# SQUID_Power.net
KiCad netlist of a schematic drawn in Altium Designer
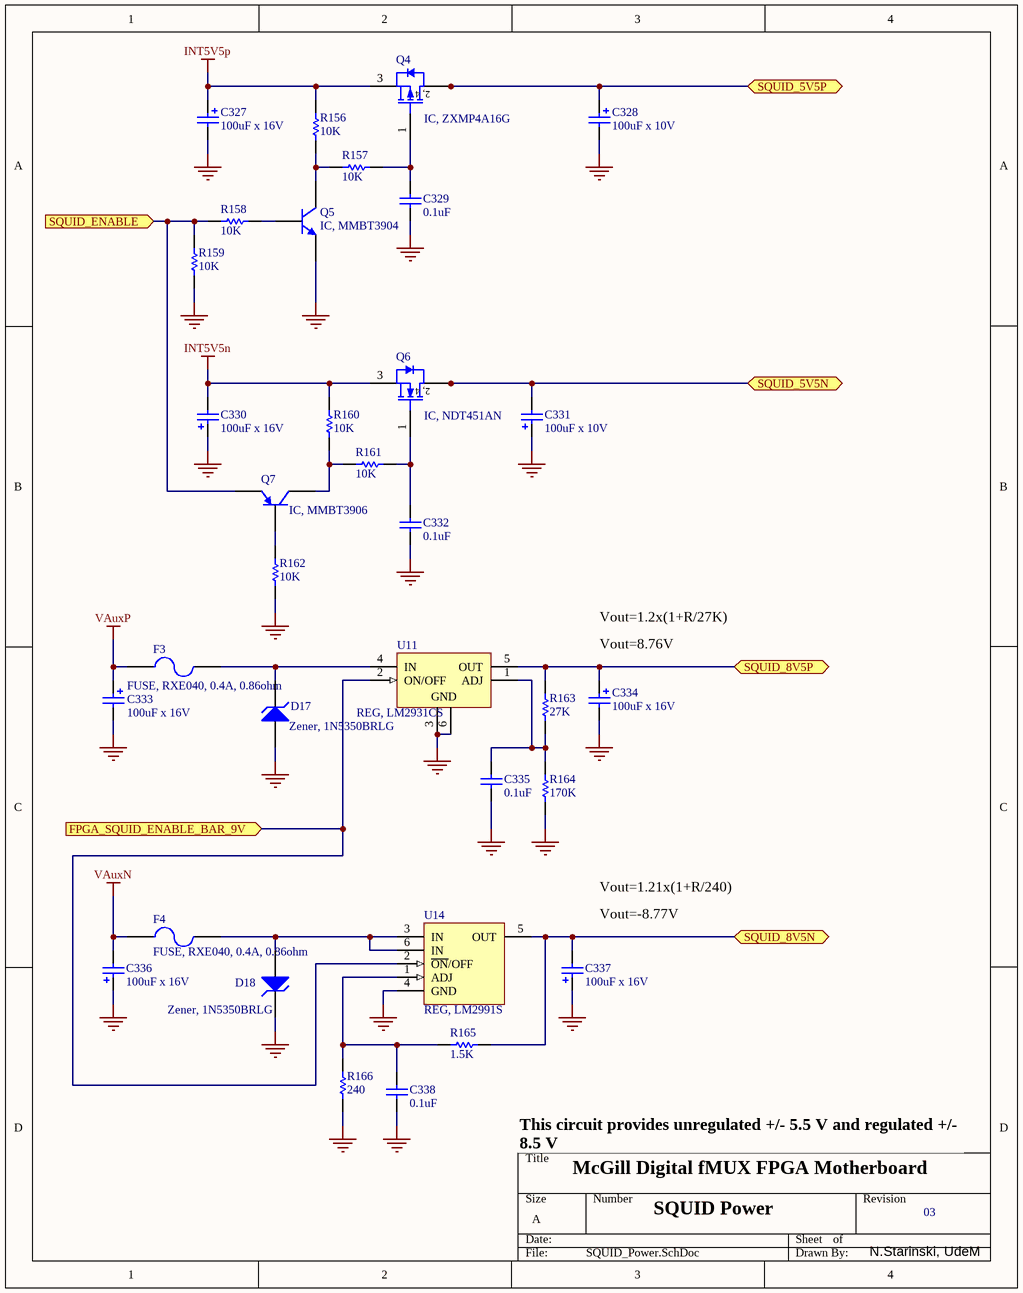
[diagram p0: SQUID_Power.SchDoc]

(export (version "E")
  (design (tool "Eeschema 10.0.6"))
  (components
    (comp (ref "C327")
      (value "100uF x 16V")
      (footprint "CC7343-31_Dsize")
      (description "CAP TANTD TPSD107M016R0060")
      (fields (field (name "PUBLISHER") "Altium Limited"))
      (libsource (lib "Miscellaneous Devices") (part "Cap Pol3"))
    )
    (comp (ref "C328")
      (value "100uF x 10V")
      (footprint "TC6032-2412")
      (description "CAP TANTC TPSC107K010R0075")
      (fields (field (name "PUBLISHER") "Altium Limited"))
      (libsource (lib "Miscellaneous Devices 02") (part "Cap Pol3"))
    )
    (comp (ref "C329")
      (value "0.1uF")
      (footprint "CC1608-0603")
      (description "Capacitor (Semiconductor SIM Model)")
      (fields (field (name "PUBLISHER") "Altium Limited"))
      (libsource (lib "Miscellaneous Devices") (part "Cap Semi"))
    )
    (comp (ref "C330")
      (value "100uF x 16V")
      (footprint "CC7343-31_Dsize")
      (description "CAP TANTD TPSD107M016R0060")
      (fields (field (name "PUBLISHER") "Altium Limited"))
      (libsource (lib "Miscellaneous Devices") (part "Cap Pol3"))
    )
    (comp (ref "C331")
      (value "100uF x 10V")
      (footprint "TC6032-2412")
      (description "CAP TANTC TPSC107K010R0075")
      (fields (field (name "PUBLISHER") "Altium Limited"))
      (libsource (lib "Miscellaneous Devices 02") (part "Cap Pol3"))
    )
    (comp (ref "C332")
      (value "0.1uF")
      (footprint "CC1608-0603")
      (description "Capacitor (Semiconductor SIM Model)")
      (fields (field (name "PUBLISHER") "Altium Limited"))
      (libsource (lib "Miscellaneous Devices") (part "Cap Semi"))
    )
    (comp (ref "C333")
      (value "100uF x 16V")
      (footprint "CC7343-31_Dsize")
      (description "CAP TANTD TPSD107M016R0060")
      (fields (field (name "PUBLISHER") "Altium Limited"))
      (libsource (lib "Miscellaneous Devices") (part "Cap Pol3"))
    )
    (comp (ref "C334")
      (value "100uF x 16V")
      (footprint "CC7343-31_Dsize")
      (description "CAP TANTD TPSD107M016R0060")
      (fields (field (name "PUBLISHER") "Altium Limited"))
      (libsource (lib "Miscellaneous Devices") (part "Cap Pol3"))
    )
    (comp (ref "C335")
      (value "0.1uF")
      (footprint "CC1608-0603")
      (description "Capacitor (Semiconductor SIM Model)")
      (fields (field (name "PUBLISHER") "Altium Limited"))
      (libsource (lib "Miscellaneous Devices") (part "Cap Semi"))
    )
    (comp (ref "C336")
      (value "100uF x 16V")
      (footprint "CC7343-31_Dsize")
      (description "CAP TANTD TPSD107M016R0060")
      (fields (field (name "PUBLISHER") "Altium Limited"))
      (libsource (lib "Miscellaneous Devices") (part "Cap Pol3"))
    )
    (comp (ref "C337")
      (value "100uF x 16V")
      (footprint "CC7343-31_Dsize")
      (description "CAP TANTD TPSD107M016R0060")
      (fields (field (name "PUBLISHER") "Altium Limited"))
      (libsource (lib "Miscellaneous Devices") (part "Cap Pol3"))
    )
    (comp (ref "C338")
      (value "0.1uF")
      (footprint "CC1608-0603")
      (description "Capacitor (Semiconductor SIM Model)")
      (fields (field (name "PUBLISHER") "Altium Limited"))
      (libsource (lib "Miscellaneous Devices") (part "Cap Semi"))
    )
    (comp (ref "D17")
      (value "Zener, 1N5350BRLG")
      (footprint "A-500")
      (description "Zener Diode, 13V, 5W")
      (fields (field (name "PUBLISHER") "Altium Limited"))
      (libsource (lib "Vishay Lite-On Discrete Diode") (part "1N5350B"))
    )
    (comp (ref "D18")
      (value "Zener, 1N5350BRLG")
      (footprint "A-500")
      (description "Zener Diode, 13V, 5W")
      (fields (field (name "PUBLISHER") "Altium Limited"))
      (libsource (lib "Vishay Lite-On Discrete Diode") (part "1N5350B"))
    )
    (comp (ref "F3")
      (value "FUSE, RXE040, 0.4A, 0.86ohm")
      (footprint "Fuse 5.88mm")
      (description "Fuse")
      (fields (field (name "PUBLISHER") "Altium Limited"))
      (libsource (lib "Miscellaneous Devices 02") (part "Fuse 2"))
    )
    (comp (ref "F4")
      (value "FUSE, RXE040, 0.4A, 0.86ohm")
      (footprint "Fuse 5.88mm")
      (description "Fuse")
      (fields (field (name "PUBLISHER") "Altium Limited"))
      (libsource (lib "Miscellaneous Devices 02") (part "Fuse 2"))
    )
    (comp (ref "Q4")
      (value "IC, ZXMP4A16G")
      (footprint "SOT223")
      (description "40V P-Channel Enhancement Mode MOSFET")
      (fields (field (name "PUBLISHER") "Altium Limited"))
      (libsource (lib "Zetex Discrete MOSFET") (part "ZXMP4A16G"))
    )
    (comp (ref "Q5")
      (value "IC, MMBT3904")
      (footprint "SOT23")
      (description "NPN Switching Transistor")
      (fields (field (name "PUBLISHER") "Altium Limited"))
      (libsource (lib "Philips Discrete BJT - Low Power") (part "MMBT3904"))
    )
    (comp (ref "Q6")
      (value "IC, NDT451AN")
      (footprint "SOT223")
      (description "100V N-Channel Enhancement Mode MOSFET")
      (fields (field (name "PUBLISHER") "Altium Limited"))
      (libsource (lib "Zetex Discrete MOSFET") (part "ZXMN10A11G"))
    )
    (comp (ref "Q7")
      (value "IC, MMBT3906")
      (footprint "SOT23")
      (description "PNP Switching Transistor")
      (fields (field (name "PUBLISHER") "Altium Limited"))
      (libsource (lib "Philips Discrete BJT - Low Power") (part "MMBT3906"))
    )
    (comp (ref "R156")
      (value "10K")
      (footprint "CR1608-0603")
      (description "Resistor 0603")
      (fields (field (name "PUBLISHER") "Altium Limited"))
      (libsource (lib "Miscellaneous Devices") (part "Res Semi"))
    )
    (comp (ref "R157")
      (value "10K")
      (footprint "CR1608-0603")
      (description "Resistor 0603")
      (fields (field (name "PUBLISHER") "Altium Limited"))
      (libsource (lib "Miscellaneous Devices") (part "Res Semi"))
    )
    (comp (ref "R158")
      (value "10K")
      (footprint "CR1608-0603")
      (description "Resistor 0603")
      (fields (field (name "PUBLISHER") "Altium Limited"))
      (libsource (lib "Miscellaneous Devices") (part "Res Semi"))
    )
    (comp (ref "R159")
      (value "10K")
      (footprint "CR1608-0603")
      (description "Resistor 0603")
      (fields (field (name "PUBLISHER") "Altium Limited"))
      (libsource (lib "Miscellaneous Devices") (part "Res Semi"))
    )
    (comp (ref "R160")
      (value "10K")
      (footprint "CR1608-0603")
      (description "Resistor 0603")
      (fields (field (name "PUBLISHER") "Altium Limited"))
      (libsource (lib "Miscellaneous Devices") (part "Res Semi"))
    )
    (comp (ref "R161")
      (value "10K")
      (footprint "CR1608-0603")
      (description "Resistor 0603")
      (fields (field (name "PUBLISHER") "Altium Limited"))
      (libsource (lib "Miscellaneous Devices") (part "Res Semi"))
    )
    (comp (ref "R162")
      (value "10K")
      (footprint "CR1608-0603")
      (description "Resistor 0603")
      (fields (field (name "PUBLISHER") "Altium Limited"))
      (libsource (lib "Miscellaneous Devices") (part "Res Semi"))
    )
    (comp (ref "R163")
      (value "27K")
      (footprint "CR1608-0603")
      (description "Resistor 0603")
      (fields (field (name "PUBLISHER") "Altium Limited"))
      (libsource (lib "Miscellaneous Devices") (part "Res Semi"))
    )
    (comp (ref "R164")
      (value "170K")
      (footprint "CR1608-0603")
      (description "Resistor 0603")
      (fields (field (name "PUBLISHER") "Altium Limited"))
      (libsource (lib "Miscellaneous Devices") (part "Res Semi"))
    )
    (comp (ref "R165")
      (value "1.5K")
      (footprint "CR1608-0603")
      (description "Resistor 0603")
      (fields (field (name "PUBLISHER") "Altium Limited"))
      (libsource (lib "Miscellaneous Devices") (part "Res Semi"))
    )
    (comp (ref "R166")
      (value "240")
      (footprint "CR1608-0603")
      (description "Resistor 0603")
      (fields (field (name "PUBLISHER") "Altium Limited"))
      (libsource (lib "Miscellaneous Devices") (part "Res Semi"))
    )
    (comp (ref "U11")
      (value "REG, LM2931CS")
      (footprint "TS5B")
      (description "Series Low-Dropout Regulator")
      (fields (field (name "PUBLISHER") "Altium Limited"))
      (libsource (lib "NSC Power Mgt Voltage Regulator") (part "LM2931CS"))
    )
    (comp (ref "U14")
      (value "REG, LM2991S")
      (footprint "TS5B")
      (description "Negative Low-Dropout Adjustable Regulator")
      (fields (field (name "PUBLISHER") "Altium Limited"))
      (libsource (lib "NSC Power Mgt Voltage Regulator") (part "LM2991S"))
    )
  )
  (nets
    (net (code "1") (name "/FPGA_SQUID_ENABLE_BAR_9V") (class "Default")
      (node (ref "U11") (pin "2") (pinfunction "ON/OFF_2") (pintype "input"))
      (node (ref "U14") (pin "2") (pinfunction "~{ON}/OFF_2") (pintype "input"))
    )
    (net (code "2") (name "/SQUID_5V5N") (class "Default")
      (node (ref "C331") (pin "2") (pinfunction "2_2") (pintype "passive"))
      (node (ref "Q6") (pin "2") (pinfunction "D_2") (pintype "passive"))
      (node (ref "Q6") (pin "4") (pinfunction "D_4") (pintype "passive"))
    )
    (net (code "3") (name "/SQUID_5V5P") (class "Default")
      (node (ref "C328") (pin "1") (pinfunction "1_1") (pintype "passive"))
      (node (ref "Q4") (pin "2") (pinfunction "D_2") (pintype "passive"))
      (node (ref "Q4") (pin "4") (pinfunction "D_4") (pintype "passive"))
    )
    (net (code "4") (name "/SQUID_8V5N") (class "Default")
      (node (ref "C337") (pin "2") (pinfunction "2_2") (pintype "passive"))
      (node (ref "R165") (pin "2") (pinfunction "2_2") (pintype "passive"))
      (node (ref "U14") (pin "5") (pinfunction "OUT_5") (pintype "power_in"))
    )
    (net (code "5") (name "/SQUID_8V5P") (class "Default")
      (node (ref "C334") (pin "1") (pinfunction "1_1") (pintype "passive"))
      (node (ref "R163") (pin "2") (pinfunction "2_2") (pintype "passive"))
      (node (ref "U11") (pin "5") (pinfunction "OUT_5") (pintype "power_in"))
    )
    (net (code "6") (name "/SQUID_ENABLE") (class "Default")
      (node (ref "Q7") (pin "2") (pinfunction "E_2") (pintype "passive"))
      (node (ref "R158") (pin "1") (pinfunction "1_1") (pintype "passive"))
      (node (ref "R159") (pin "2") (pinfunction "2_2") (pintype "passive"))
    )
    (net (code "7") (name "GND") (class "Default")
      (node (ref "C327") (pin "2") (pinfunction "2_2") (pintype "passive"))
      (node (ref "C328") (pin "2") (pinfunction "2_2") (pintype "passive"))
      (node (ref "C329") (pin "1") (pinfunction "1_1") (pintype "passive"))
      (node (ref "C330") (pin "1") (pinfunction "1_1") (pintype "passive"))
      (node (ref "C331") (pin "1") (pinfunction "1_1") (pintype "passive"))
      (node (ref "C332") (pin "1") (pinfunction "1_1") (pintype "passive"))
      (node (ref "C333") (pin "2") (pinfunction "2_2") (pintype "passive"))
      (node (ref "C334") (pin "2") (pinfunction "2_2") (pintype "passive"))
      (node (ref "C335") (pin "1") (pinfunction "1_1") (pintype "passive"))
      (node (ref "C336") (pin "1") (pinfunction "1_1") (pintype "passive"))
      (node (ref "C337") (pin "1") (pinfunction "1_1") (pintype "passive"))
      (node (ref "C338") (pin "1") (pinfunction "1_1") (pintype "passive"))
      (node (ref "D17") (pin "1") (pinfunction "A_1") (pintype "passive"))
      (node (ref "D18") (pin "2") (pinfunction "K_2") (pintype "passive"))
      (node (ref "Q5") (pin "2") (pinfunction "E_2") (pintype "passive"))
      (node (ref "R159") (pin "1") (pinfunction "1_1") (pintype "passive"))
      (node (ref "R162") (pin "1") (pinfunction "1_1") (pintype "passive"))
      (node (ref "R164") (pin "1") (pinfunction "1_1") (pintype "passive"))
      (node (ref "R166") (pin "1") (pinfunction "1_1") (pintype "passive"))
      (node (ref "U11") (pin "3") (pinfunction "GND_3") (pintype "power_in"))
      (node (ref "U11") (pin "6") (pinfunction "GND_(TAB)_6") (pintype "power_in"))
      (node (ref "U14") (pin "4") (pinfunction "GND_4") (pintype "power_in"))
    )
    (net (code "8") (name "INT5V5n") (class "Default")
      (node (ref "C330") (pin "2") (pinfunction "2_2") (pintype "passive"))
      (node (ref "Q6") (pin "3") (pinfunction "S_3") (pintype "passive"))
      (node (ref "R160") (pin "2") (pinfunction "2_2") (pintype "passive"))
    )
    (net (code "9") (name "INT5V5p") (class "Default")
      (node (ref "C327") (pin "1") (pinfunction "1_1") (pintype "passive"))
      (node (ref "Q4") (pin "3") (pinfunction "S_3") (pintype "passive"))
      (node (ref "R156") (pin "2") (pinfunction "2_2") (pintype "passive"))
    )
    (net (code "10") (name "Net-(D17-K)") (class "Default")
      (node (ref "D17") (pin "2") (pinfunction "K_2") (pintype "passive"))
      (node (ref "F3") (pin "2") (pinfunction "2_2") (pintype "passive"))
      (node (ref "U11") (pin "4") (pinfunction "IN_4") (pintype "power_in"))
    )
    (net (code "11") (name "Net-(D18-A)") (class "Default")
      (node (ref "D18") (pin "1") (pinfunction "A_1") (pintype "passive"))
      (node (ref "F4") (pin "2") (pinfunction "2_2") (pintype "passive"))
      (node (ref "U14") (pin "3") (pinfunction "IN_3") (pintype "power_in"))
      (node (ref "U14") (pin "6") (pinfunction "IN_6") (pintype "power_in"))
    )
    (net (code "12") (name "Net-(Q4-G)") (class "Default")
      (node (ref "C329") (pin "2") (pinfunction "2_2") (pintype "passive"))
      (node (ref "Q4") (pin "1") (pinfunction "G_1") (pintype "passive"))
      (node (ref "R157") (pin "2") (pinfunction "2_2") (pintype "passive"))
    )
    (net (code "13") (name "Net-(Q5-B)") (class "Default")
      (node (ref "Q5") (pin "1") (pinfunction "B_1") (pintype "passive"))
      (node (ref "R158") (pin "2") (pinfunction "2_2") (pintype "passive"))
    )
    (net (code "14") (name "Net-(Q5-C)") (class "Default")
      (node (ref "Q5") (pin "3") (pinfunction "C_3") (pintype "passive"))
      (node (ref "R156") (pin "1") (pinfunction "1_1") (pintype "passive"))
      (node (ref "R157") (pin "1") (pinfunction "1_1") (pintype "passive"))
    )
    (net (code "15") (name "Net-(Q6-G)") (class "Default")
      (node (ref "C332") (pin "2") (pinfunction "2_2") (pintype "passive"))
      (node (ref "Q6") (pin "1") (pinfunction "G_1") (pintype "passive"))
      (node (ref "R161") (pin "2") (pinfunction "2_2") (pintype "passive"))
    )
    (net (code "16") (name "Net-(Q7-B)") (class "Default")
      (node (ref "Q7") (pin "1") (pinfunction "B_1") (pintype "passive"))
      (node (ref "R162") (pin "2") (pinfunction "2_2") (pintype "passive"))
    )
    (net (code "17") (name "Net-(Q7-C)") (class "Default")
      (node (ref "Q7") (pin "3") (pinfunction "C_3") (pintype "passive"))
      (node (ref "R160") (pin "1") (pinfunction "1_1") (pintype "passive"))
      (node (ref "R161") (pin "1") (pinfunction "1_1") (pintype "passive"))
    )
    (net (code "18") (name "Net-(U11-ADJ)") (class "Default")
      (node (ref "C335") (pin "2") (pinfunction "2_2") (pintype "passive"))
      (node (ref "R163") (pin "1") (pinfunction "1_1") (pintype "passive"))
      (node (ref "R164") (pin "2") (pinfunction "2_2") (pintype "passive"))
      (node (ref "U11") (pin "1") (pinfunction "ADJ_1") (pintype "passive"))
    )
    (net (code "19") (name "Net-(U14-ADJ)") (class "Default")
      (node (ref "C338") (pin "2") (pinfunction "2_2") (pintype "passive"))
      (node (ref "R165") (pin "1") (pinfunction "1_1") (pintype "passive"))
      (node (ref "R166") (pin "2") (pinfunction "2_2") (pintype "passive"))
      (node (ref "U14") (pin "1") (pinfunction "ADJ_1") (pintype "input"))
    )
    (net (code "20") (name "VAuxN") (class "Default")
      (node (ref "C336") (pin "2") (pinfunction "2_2") (pintype "passive"))
      (node (ref "F4") (pin "1") (pinfunction "1_1") (pintype "passive"))
    )
    (net (code "21") (name "VAuxP") (class "Default")
      (node (ref "C333") (pin "1") (pinfunction "1_1") (pintype "passive"))
      (node (ref "F3") (pin "1") (pinfunction "1_1") (pintype "passive"))
    )
  )
)
